# taximeter.net
KiCad netlist of a schematic drawn in Altium Designer
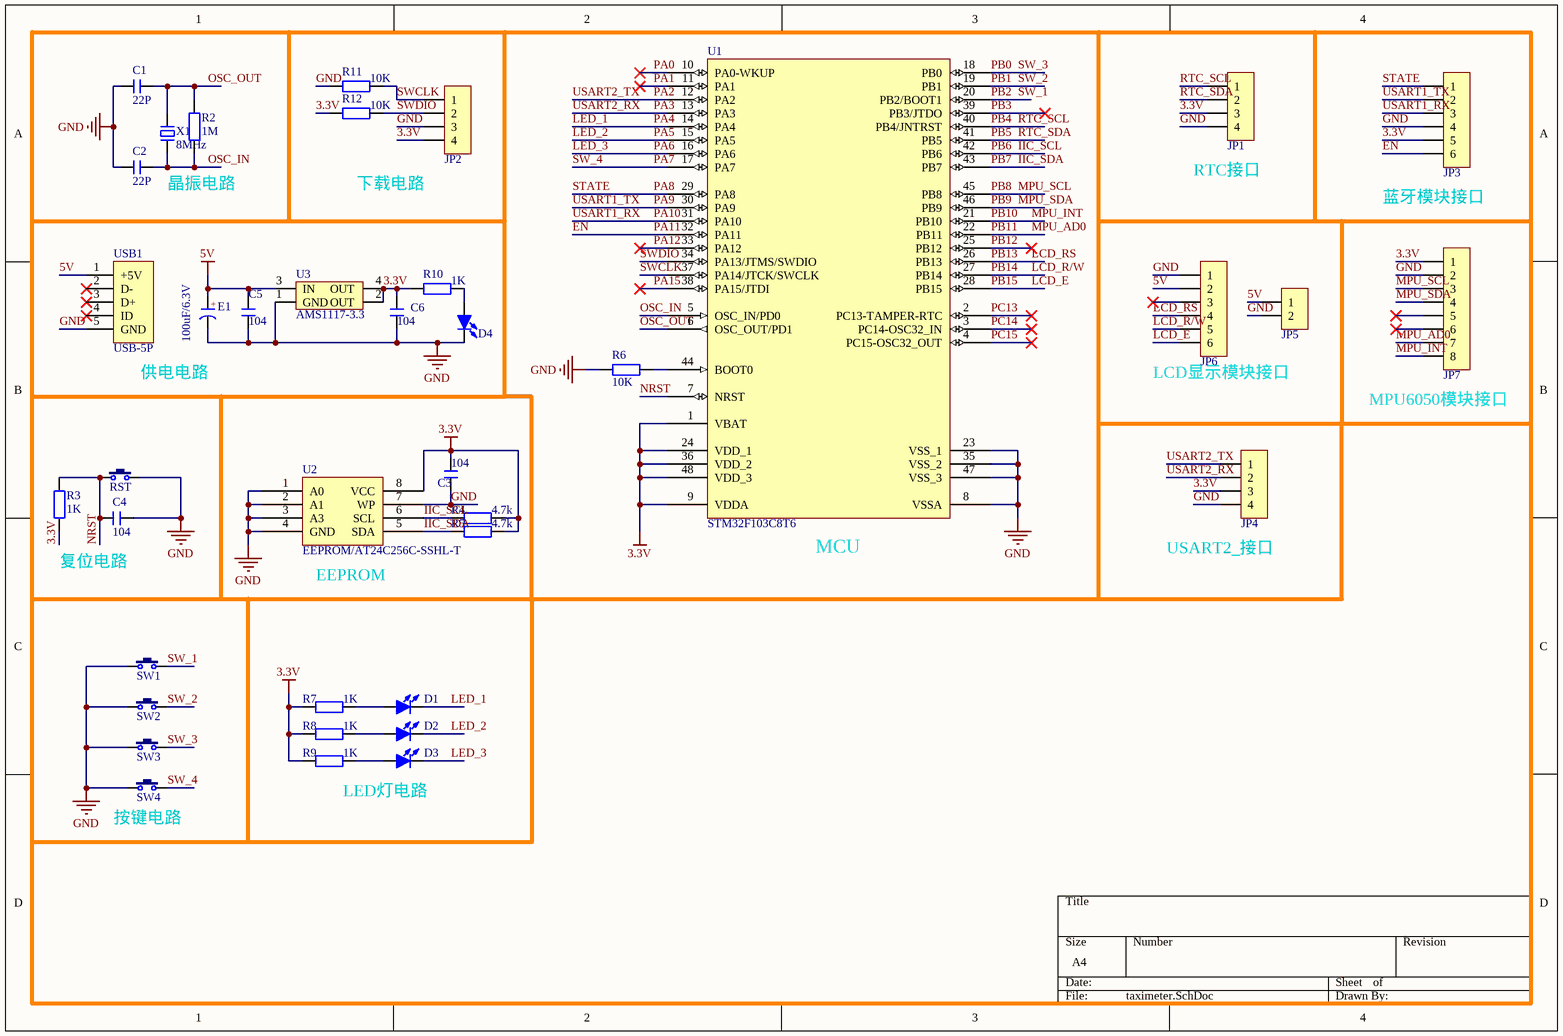
[diagram p0: taximeter.SchDoc]

(export (version "E")
  (design (tool "Eeschema 10.0.6"))
  (components
    (comp (ref "C1")
      (value "22P")
      (footprint "C 0805")
      (description "无极性贴片电容")
      (fields (field (name "版权归属") "源创客"))
      (libsource (lib "电阻-电容-电感") (part "C"))
    )
    (comp (ref "C2")
      (value "22P")
      (footprint "C 0805")
      (description "无极性贴片电容")
      (fields (field (name "版权归属") "源创客"))
      (libsource (lib "电阻-电容-电感") (part "C"))
    )
    (comp (ref "C3")
      (value "104")
      (footprint "C 0805")
      (description "无极性贴片电容")
      (fields (field (name "版权归属") "源创客"))
      (libsource (lib "电阻-电容-电感") (part "C"))
    )
    (comp (ref "C4")
      (value "104")
      (footprint "C 0805")
      (description "无极性贴片电容")
      (fields (field (name "版权归属") "源创客"))
      (libsource (lib "电阻-电容-电感") (part "C"))
    )
    (comp (ref "C5")
      (value "104")
      (footprint "C 0805")
      (description "无极性贴片电容")
      (fields (field (name "版权归属") "源创客"))
      (libsource (lib "电阻-电容-电感") (part "C"))
    )
    (comp (ref "C6")
      (value "104")
      (footprint "C 0805")
      (description "无极性贴片电容")
      (fields (field (name "版权归属") "源创客"))
      (libsource (lib "电阻-电容-电感") (part "C"))
    )
    (comp (ref "D1")
      (value "蓝色")
      (footprint "LED 0805G")
      (description "贴片LED")
      (fields (field (name "版权归属") "源创客"))
      (libsource (lib "LED") (part "LED-SMD"))
    )
    (comp (ref "D2")
      (value "蓝色")
      (footprint "LED 0805G")
      (description "贴片LED")
      (fields (field (name "版权归属") "源创客"))
      (libsource (lib "LED") (part "LED-SMD"))
    )
    (comp (ref "D3")
      (value "蓝色")
      (footprint "LED 0805G")
      (description "贴片LED")
      (fields (field (name "版权归属") "源创客"))
      (libsource (lib "LED") (part "LED-SMD"))
    )
    (comp (ref "D4")
      (value "红色")
      (footprint "LED 0805G")
      (description "贴片LED")
      (fields (field (name "版权归属") "源创客"))
      (libsource (lib "LED") (part "LED-SMD"))
    )
    (comp (ref "E1")
      (value "100uF/6.3V")
      (footprint "CD A(3216)")
      (description "贴片钽电容")
      (fields (field (name "版权归属") "源创客"))
      (libsource (lib "电阻-电容-电感") (part "C-CD"))
    )
    (comp (ref "JP1")
      (value "HDR-1X4")
      (footprint "HDR-1X4")
      (description "4P接插件")
      (fields (field (name "版权归属") "源创客"))
      (libsource (lib "接插件") (part "Header 4"))
    )
    (comp (ref "JP2")
      (value "HDR-1X4")
      (footprint "HDR-1X4")
      (description "4P接插件")
      (fields (field (name "版权归属") "源创客"))
      (libsource (lib "接插件") (part "Header 4"))
    )
    (comp (ref "JP3")
      (value "HDR-1X6")
      (footprint "HDR-1X6")
      (description "6P接插件")
      (fields (field (name "版权归属") "源创客"))
      (libsource (lib "接插件") (part "Header 6"))
    )
    (comp (ref "JP4")
      (value "HDR-1X4")
      (footprint "HDR-1X4")
      (description "4P接插件")
      (fields (field (name "版权归属") "源创客"))
      (libsource (lib "接插件") (part "Header 4"))
    )
    (comp (ref "JP5")
      (value "HDR-1X2")
      (footprint "HDR-1X2")
      (description "2P接插件")
      (fields (field (name "版权归属") "源创客"))
      (libsource (lib "接插件") (part "Header 2"))
    )
    (comp (ref "JP6")
      (value "HDR-1X6")
      (footprint "HDR-1X6")
      (description "6P接插件")
      (fields (field (name "版权归属") "源创客"))
      (libsource (lib "接插件") (part "Header 6"))
    )
    (comp (ref "JP7")
      (value "HDR-1X8")
      (footprint "HDR-1X8")
      (description "8P接插件")
      (fields (field (name "版权归属") "源创客"))
      (libsource (lib "接插件") (part "Header 8"))
    )
    (comp (ref "R2")
      (value "1M")
      (footprint "R 0805")
      (description "贴片电阻")
      (fields (field (name "版权归属") "源创客"))
      (libsource (lib "电阻-电容-电感") (part "R"))
    )
    (comp (ref "R3")
      (value "1K")
      (footprint "R 0805")
      (description "贴片电阻")
      (fields (field (name "版权归属") "源创客"))
      (libsource (lib "电阻-电容-电感") (part "R"))
    )
    (comp (ref "R4")
      (value "4.7k")
      (footprint "R 0805")
      (description "贴片电阻")
      (fields (field (name "版权归属") "源创客"))
      (libsource (lib "电阻-电容-电感") (part "R"))
    )
    (comp (ref "R5")
      (value "4.7k")
      (footprint "R 0805")
      (description "贴片电阻")
      (fields (field (name "版权归属") "源创客"))
      (libsource (lib "电阻-电容-电感") (part "R"))
    )
    (comp (ref "R6")
      (value "10K")
      (footprint "R 0805")
      (description "贴片电阻")
      (fields (field (name "版权归属") "源创客"))
      (libsource (lib "电阻-电容-电感") (part "R"))
    )
    (comp (ref "R7")
      (value "1K")
      (footprint "R 0805")
      (description "贴片电阻")
      (fields (field (name "版权归属") "源创客"))
      (libsource (lib "电阻-电容-电感") (part "R"))
    )
    (comp (ref "R8")
      (value "1K")
      (footprint "R 0805")
      (description "贴片电阻")
      (fields (field (name "版权归属") "源创客"))
      (libsource (lib "电阻-电容-电感") (part "R"))
    )
    (comp (ref "R9")
      (value "1K")
      (footprint "R 0805")
      (description "贴片电阻")
      (fields (field (name "版权归属") "源创客"))
      (libsource (lib "电阻-电容-电感") (part "R"))
    )
    (comp (ref "R10")
      (value "1K")
      (footprint "R 0805")
      (description "贴片电阻")
      (fields (field (name "版权归属") "源创客"))
      (libsource (lib "电阻-电容-电感") (part "R"))
    )
    (comp (ref "R11")
      (value "10K")
      (footprint "R 0805")
      (description "贴片电阻")
      (fields (field (name "版权归属") "源创客"))
      (libsource (lib "电阻-电容-电感") (part "R"))
    )
    (comp (ref "R12")
      (value "10K")
      (footprint "R 0805")
      (description "贴片电阻")
      (fields (field (name "版权归属") "源创客"))
      (libsource (lib "电阻-电容-电感") (part "R"))
    )
    (comp (ref "RST")
      (value "3x6x5")
      (footprint "TSW DIP-3*6*5_V")
      (description "3x6轻触开关")
      (fields (field (name "版权归属") "源创客"))
      (libsource (lib "按键-开关") (part "TSW 3x6"))
    )
    (comp (ref "SW1")
      (value "3x6x5")
      (footprint "TSW DIP-3*6*5_V")
      (description "3x6轻触开关")
      (fields (field (name "版权归属") "源创客"))
      (libsource (lib "按键-开关") (part "TSW 3x6"))
    )
    (comp (ref "SW2")
      (value "3x6x5")
      (footprint "TSW DIP-3*6*5_V")
      (description "3x6轻触开关")
      (fields (field (name "版权归属") "源创客"))
      (libsource (lib "按键-开关") (part "TSW 3x6"))
    )
    (comp (ref "SW3")
      (value "3x6x5")
      (footprint "TSW DIP-3*6*5_V")
      (description "3x6轻触开关")
      (fields (field (name "版权归属") "源创客"))
      (libsource (lib "按键-开关") (part "TSW 3x6"))
    )
    (comp (ref "SW4")
      (value "3x6x5")
      (footprint "TSW DIP-3*6*5_V")
      (description "3x6轻触开关")
      (fields (field (name "版权归属") "源创客"))
      (libsource (lib "按键-开关") (part "TSW 3x6"))
    )
    (comp (ref "U1")
      (value "STM32F103C8T6")
      (footprint "LQFP48 7X7_M")
      (description "Flaah:64/RAM:20/IO:36")
      (fields (field (name "版权归属") "源创客"))
      (libsource (lib "STM32系列单片机") (part "STM32F103C8T6"))
    )
    (comp (ref "U2")
      (value "EEPROM/AT24C256C-SSHL-T")
      (footprint "LC-SOIC-8_150mil")
      (description "EEPROM")
      (libsource (lib "Miscellaneous Devices LC") (part "EEPROM/AT24C256C-SSHL-T"))
    )
    (comp (ref "U3")
      (value "AMS1117-3.3")
      (footprint "AMS1117")
      (libsource (lib "ATK-VS1053 MP3") (part "AMS1117"))
    )
    (comp (ref "USB1")
      (value "USB-5P")
      (footprint "USB-MICRO_B")
      (description "微型USB母座")
      (fields (field (name "版权归属") "源创客"))
      (libsource (lib "接口类") (part "USB-5P"))
    )
    (comp (ref "X1")
      (value "8MHz")
      (footprint "XTAL-49S SMD")
      (description "2脚晶振")
      (fields (field (name "版权归属") "源创客"))
      (libsource (lib "保险丝-晶振") (part "XTAL-2"))
    )
  )
  (nets
    (net (code "1") (name "/EN") (class "Default")
      (node (ref "JP3") (pin "6") (pinfunction "6_6") (pintype "passive"))
      (node (ref "U1") (pin "32") (pinfunction "PA11_32") (pintype "bidirectional"))
    )
    (net (code "2") (name "/IIC_SCL") (class "Default")
      (node (ref "R4") (pin "1") (pinfunction "1_1") (pintype "passive"))
      (node (ref "U1") (pin "42") (pinfunction "PB6_42") (pintype "bidirectional"))
      (node (ref "U2") (pin "6") (pinfunction "SCL_6") (pintype "passive"))
    )
    (net (code "3") (name "/IIC_SDA") (class "Default")
      (node (ref "R5") (pin "1") (pinfunction "1_1") (pintype "passive"))
      (node (ref "U1") (pin "43") (pinfunction "PB7_43") (pintype "bidirectional"))
      (node (ref "U2") (pin "5") (pinfunction "SDA_5") (pintype "passive"))
    )
    (net (code "4") (name "/LCD_E") (class "Default")
      (node (ref "JP6") (pin "6") (pinfunction "6_6") (pintype "passive"))
      (node (ref "U1") (pin "28") (pinfunction "PB15_28") (pintype "bidirectional"))
    )
    (net (code "5") (name "/LCD_RS") (class "Default")
      (node (ref "JP6") (pin "4") (pinfunction "4_4") (pintype "passive"))
      (node (ref "U1") (pin "26") (pinfunction "PB13_26") (pintype "bidirectional"))
    )
    (net (code "6") (name "/LCD_R{slash}W") (class "Default")
      (node (ref "JP6") (pin "5") (pinfunction "5_5") (pintype "passive"))
      (node (ref "U1") (pin "27") (pinfunction "PB14_27") (pintype "bidirectional"))
    )
    (net (code "7") (name "/LED_1") (class "Default")
      (node (ref "D1") (pin "2") (pinfunction "K_2") (pintype "passive"))
      (node (ref "U1") (pin "14") (pinfunction "PA4_14") (pintype "bidirectional"))
    )
    (net (code "8") (name "/LED_2") (class "Default")
      (node (ref "D2") (pin "2") (pinfunction "K_2") (pintype "passive"))
      (node (ref "U1") (pin "15") (pinfunction "PA5_15") (pintype "bidirectional"))
    )
    (net (code "9") (name "/LED_3") (class "Default")
      (node (ref "D3") (pin "2") (pinfunction "K_2") (pintype "passive"))
      (node (ref "U1") (pin "16") (pinfunction "PA6_16") (pintype "bidirectional"))
    )
    (net (code "10") (name "/MPU_AD0") (class "Default")
      (node (ref "JP7") (pin "7") (pinfunction "7_7") (pintype "passive"))
      (node (ref "U1") (pin "22") (pinfunction "PB11_22") (pintype "bidirectional"))
    )
    (net (code "11") (name "/MPU_INT") (class "Default")
      (node (ref "JP7") (pin "8") (pinfunction "8_8") (pintype "passive"))
      (node (ref "U1") (pin "21") (pinfunction "PB10_21") (pintype "bidirectional"))
    )
    (net (code "12") (name "/MPU_SCL") (class "Default")
      (node (ref "JP7") (pin "3") (pinfunction "3_3") (pintype "passive"))
      (node (ref "U1") (pin "45") (pinfunction "PB8_45") (pintype "bidirectional"))
    )
    (net (code "13") (name "/MPU_SDA") (class "Default")
      (node (ref "JP7") (pin "4") (pinfunction "4_4") (pintype "passive"))
      (node (ref "U1") (pin "46") (pinfunction "PB9_46") (pintype "bidirectional"))
    )
    (net (code "14") (name "/NRST") (class "Default")
      (node (ref "C4") (pin "1") (pinfunction "1_1") (pintype "passive"))
      (node (ref "R3") (pin "2") (pinfunction "2_2") (pintype "passive"))
      (node (ref "RST") (pin "1") (pinfunction "1_1") (pintype "passive"))
      (node (ref "U1") (pin "7") (pinfunction "NRST_7") (pintype "bidirectional"))
    )
    (net (code "15") (name "/OSC_IN") (class "Default")
      (node (ref "C2") (pin "2") (pinfunction "2_2") (pintype "passive"))
      (node (ref "R2") (pin "2") (pinfunction "2_2") (pintype "passive"))
      (node (ref "U1") (pin "5") (pinfunction "OSC_IN/PD0_5") (pintype "input"))
      (node (ref "X1") (pin "2") (pinfunction "2_2") (pintype "passive"))
    )
    (net (code "16") (name "/OSC_OUT") (class "Default")
      (node (ref "C1") (pin "2") (pinfunction "2_2") (pintype "passive"))
      (node (ref "R2") (pin "1") (pinfunction "1_1") (pintype "passive"))
      (node (ref "U1") (pin "6") (pinfunction "OSC_OUT/PD1_6") (pintype "output"))
      (node (ref "X1") (pin "1") (pinfunction "1_1") (pintype "passive"))
    )
    (net (code "17") (name "/PA0") (class "Default")
      (node (ref "U1") (pin "10") (pinfunction "PA0-WKUP_10") (pintype "bidirectional+no_connect"))
    )
    (net (code "18") (name "/PA1") (class "Default")
      (node (ref "U1") (pin "11") (pinfunction "PA1_11") (pintype "bidirectional+no_connect"))
    )
    (net (code "19") (name "/PA2") (class "Default")
      (node (ref "JP4") (pin "1") (pinfunction "1_1") (pintype "passive"))
      (node (ref "U1") (pin "12") (pinfunction "PA2_12") (pintype "bidirectional"))
    )
    (net (code "20") (name "/PA3") (class "Default")
      (node (ref "JP4") (pin "2") (pinfunction "2_2") (pintype "passive"))
      (node (ref "U1") (pin "13") (pinfunction "PA3_13") (pintype "bidirectional"))
    )
    (net (code "21") (name "/PA7") (class "Default")
      (node (ref "SW4") (pin "2") (pinfunction "2_2") (pintype "passive"))
      (node (ref "U1") (pin "17") (pinfunction "PA7_17") (pintype "bidirectional"))
    )
    (net (code "22") (name "/PA8") (class "Default")
      (node (ref "JP3") (pin "1") (pinfunction "1_1") (pintype "passive"))
      (node (ref "U1") (pin "29") (pinfunction "PA8_29") (pintype "bidirectional"))
    )
    (net (code "23") (name "/PA9") (class "Default")
      (node (ref "JP3") (pin "2") (pinfunction "2_2") (pintype "passive"))
      (node (ref "U1") (pin "30") (pinfunction "PA9_30") (pintype "bidirectional"))
    )
    (net (code "24") (name "/PA10") (class "Default")
      (node (ref "JP3") (pin "3") (pinfunction "3_3") (pintype "passive"))
      (node (ref "U1") (pin "31") (pinfunction "PA10_31") (pintype "bidirectional"))
    )
    (net (code "25") (name "/PA12") (class "Default")
      (node (ref "U1") (pin "33") (pinfunction "PA12_33") (pintype "bidirectional+no_connect"))
    )
    (net (code "26") (name "/PA15") (class "Default")
      (node (ref "U1") (pin "38") (pinfunction "PA15/JTDI_38") (pintype "bidirectional+no_connect"))
    )
    (net (code "27") (name "/PB0") (class "Default")
      (node (ref "SW3") (pin "2") (pinfunction "2_2") (pintype "passive"))
      (node (ref "U1") (pin "18") (pinfunction "PB0_18") (pintype "bidirectional"))
    )
    (net (code "28") (name "/PB1") (class "Default")
      (node (ref "SW2") (pin "2") (pinfunction "2_2") (pintype "passive"))
      (node (ref "U1") (pin "19") (pinfunction "PB1_19") (pintype "bidirectional"))
    )
    (net (code "29") (name "/PB2") (class "Default")
      (node (ref "SW1") (pin "2") (pinfunction "2_2") (pintype "passive"))
      (node (ref "U1") (pin "20") (pinfunction "PB2/BOOT1_20") (pintype "bidirectional"))
    )
    (net (code "30") (name "/PB3") (class "Default")
      (node (ref "U1") (pin "39") (pinfunction "PB3/JTDO_39") (pintype "bidirectional+no_connect"))
    )
    (net (code "31") (name "/PB4") (class "Default")
      (node (ref "JP1") (pin "1") (pinfunction "1_1") (pintype "passive"))
      (node (ref "U1") (pin "40") (pinfunction "PB4/JNTRST_40") (pintype "bidirectional"))
    )
    (net (code "32") (name "/PB5") (class "Default")
      (node (ref "JP1") (pin "2") (pinfunction "2_2") (pintype "passive"))
      (node (ref "U1") (pin "41") (pinfunction "PB5_41") (pintype "bidirectional"))
    )
    (net (code "33") (name "/PB12") (class "Default")
      (node (ref "U1") (pin "25") (pinfunction "PB12_25") (pintype "bidirectional+no_connect"))
    )
    (net (code "34") (name "/PC13") (class "Default")
      (node (ref "U1") (pin "2") (pinfunction "PC13-TAMPER-RTC_2") (pintype "bidirectional+no_connect"))
    )
    (net (code "35") (name "/PC14") (class "Default")
      (node (ref "U1") (pin "3") (pinfunction "PC14-OSC32_IN_3") (pintype "bidirectional+no_connect"))
    )
    (net (code "36") (name "/PC15") (class "Default")
      (node (ref "U1") (pin "4") (pinfunction "PC15-OSC32_OUT_4") (pintype "bidirectional+no_connect"))
    )
    (net (code "37") (name "/SWCLK") (class "Default")
      (node (ref "JP2") (pin "1") (pinfunction "1_1") (pintype "passive"))
      (node (ref "R11") (pin "2") (pinfunction "2_2") (pintype "passive"))
      (node (ref "U1") (pin "37") (pinfunction "PA14/JTCK/SWCLK_37") (pintype "bidirectional"))
    )
    (net (code "38") (name "/SWDIO") (class "Default")
      (node (ref "JP2") (pin "2") (pinfunction "2_2") (pintype "passive"))
      (node (ref "R12") (pin "2") (pinfunction "2_2") (pintype "passive"))
      (node (ref "U1") (pin "34") (pinfunction "PA13/JTMS/SWDIO_34") (pintype "bidirectional"))
    )
    (net (code "39") (name "3.3V") (class "Default")
      (node (ref "C3") (pin "2") (pinfunction "2_2") (pintype "passive"))
      (node (ref "C6") (pin "2") (pinfunction "2_2") (pintype "passive"))
      (node (ref "JP1") (pin "3") (pinfunction "3_3") (pintype "passive"))
      (node (ref "JP2") (pin "4") (pinfunction "4_4") (pintype "passive"))
      (node (ref "JP3") (pin "5") (pinfunction "5_5") (pintype "passive"))
      (node (ref "JP4") (pin "3") (pinfunction "3_3") (pintype "passive"))
      (node (ref "JP7") (pin "1") (pinfunction "1_1") (pintype "passive"))
      (node (ref "R10") (pin "1") (pinfunction "1_1") (pintype "passive"))
      (node (ref "R12") (pin "1") (pinfunction "1_1") (pintype "passive"))
      (node (ref "R3") (pin "1") (pinfunction "1_1") (pintype "passive"))
      (node (ref "R4") (pin "2") (pinfunction "2_2") (pintype "passive"))
      (node (ref "R5") (pin "2") (pinfunction "2_2") (pintype "passive"))
      (node (ref "R7") (pin "2") (pinfunction "2_2") (pintype "passive"))
      (node (ref "R8") (pin "2") (pinfunction "2_2") (pintype "passive"))
      (node (ref "R9") (pin "2") (pinfunction "2_2") (pintype "passive"))
      (node (ref "U1") (pin "1") (pinfunction "VBAT_1") (pintype "power_in"))
      (node (ref "U1") (pin "24") (pinfunction "VDD_1_24") (pintype "power_in"))
      (node (ref "U1") (pin "36") (pinfunction "VDD_2_36") (pintype "power_in"))
      (node (ref "U1") (pin "48") (pinfunction "VDD_3_48") (pintype "power_in"))
      (node (ref "U1") (pin "9") (pinfunction "VDDA_9") (pintype "power_in"))
      (node (ref "U2") (pin "8") (pinfunction "VCC_8") (pintype "passive"))
      (node (ref "U3") (pin "2") (pinfunction "OUT_2") (pintype "passive"))
      (node (ref "U3") (pin "4") (pinfunction "OUT_4") (pintype "passive"))
    )
    (net (code "40") (name "5V") (class "Default")
      (node (ref "C5") (pin "2") (pinfunction "2_2") (pintype "passive"))
      (node (ref "E1") (pin "1") (pinfunction "A_1") (pintype "passive"))
      (node (ref "JP5") (pin "1") (pinfunction "1_1") (pintype "passive"))
      (node (ref "JP6") (pin "2") (pinfunction "2_2") (pintype "passive"))
      (node (ref "U3") (pin "3") (pinfunction "IN_3") (pintype "passive"))
      (node (ref "USB1") (pin "1") (pinfunction "+5V_1") (pintype "passive"))
    )
    (net (code "41") (name "GND") (class "Default")
      (node (ref "C1") (pin "1") (pinfunction "1_1") (pintype "passive"))
      (node (ref "C2") (pin "1") (pinfunction "1_1") (pintype "passive"))
      (node (ref "C3") (pin "1") (pinfunction "1_1") (pintype "passive"))
      (node (ref "C4") (pin "2") (pinfunction "2_2") (pintype "passive"))
      (node (ref "C5") (pin "1") (pinfunction "1_1") (pintype "passive"))
      (node (ref "C6") (pin "1") (pinfunction "1_1") (pintype "passive"))
      (node (ref "D4") (pin "2") (pinfunction "K_2") (pintype "passive"))
      (node (ref "E1") (pin "2") (pinfunction "K_2") (pintype "passive"))
      (node (ref "JP1") (pin "4") (pinfunction "4_4") (pintype "passive"))
      (node (ref "JP2") (pin "3") (pinfunction "3_3") (pintype "passive"))
      (node (ref "JP3") (pin "4") (pinfunction "4_4") (pintype "passive"))
      (node (ref "JP4") (pin "4") (pinfunction "4_4") (pintype "passive"))
      (node (ref "JP5") (pin "2") (pinfunction "2_2") (pintype "passive"))
      (node (ref "JP6") (pin "1") (pinfunction "1_1") (pintype "passive"))
      (node (ref "JP7") (pin "2") (pinfunction "2_2") (pintype "passive"))
      (node (ref "R11") (pin "1") (pinfunction "1_1") (pintype "passive"))
      (node (ref "R6") (pin "1") (pinfunction "1_1") (pintype "passive"))
      (node (ref "RST") (pin "2") (pinfunction "2_2") (pintype "passive"))
      (node (ref "SW1") (pin "1") (pinfunction "1_1") (pintype "passive"))
      (node (ref "SW2") (pin "1") (pinfunction "1_1") (pintype "passive"))
      (node (ref "SW3") (pin "1") (pinfunction "1_1") (pintype "passive"))
      (node (ref "SW4") (pin "1") (pinfunction "1_1") (pintype "passive"))
      (node (ref "U1") (pin "23") (pinfunction "VSS_1_23") (pintype "power_in"))
      (node (ref "U1") (pin "35") (pinfunction "VSS_2_35") (pintype "power_in"))
      (node (ref "U1") (pin "47") (pinfunction "VSS_3_47") (pintype "power_in"))
      (node (ref "U1") (pin "8") (pinfunction "VSSA_8") (pintype "power_in"))
      (node (ref "U2") (pin "1") (pinfunction "A0_1") (pintype "passive"))
      (node (ref "U2") (pin "2") (pinfunction "A1_2") (pintype "passive"))
      (node (ref "U2") (pin "3") (pinfunction "A3_3") (pintype "passive"))
      (node (ref "U2") (pin "4") (pinfunction "GND_4") (pintype "passive"))
      (node (ref "U2") (pin "7") (pinfunction "WP_7") (pintype "passive"))
      (node (ref "U3") (pin "1") (pinfunction "GND_1") (pintype "passive"))
      (node (ref "USB1") (pin "5") (pinfunction "GND_5") (pintype "passive"))
    )
    (net (code "42") (name "Net-(D1-A)") (class "Default")
      (node (ref "D1") (pin "1") (pinfunction "A_1") (pintype "passive"))
      (node (ref "R7") (pin "1") (pinfunction "1_1") (pintype "passive"))
    )
    (net (code "43") (name "Net-(D2-A)") (class "Default")
      (node (ref "D2") (pin "1") (pinfunction "A_1") (pintype "passive"))
      (node (ref "R8") (pin "1") (pinfunction "1_1") (pintype "passive"))
    )
    (net (code "44") (name "Net-(D3-A)") (class "Default")
      (node (ref "D3") (pin "1") (pinfunction "A_1") (pintype "passive"))
      (node (ref "R9") (pin "1") (pinfunction "1_1") (pintype "passive"))
    )
    (net (code "45") (name "Net-(D4-A)") (class "Default")
      (node (ref "D4") (pin "1") (pinfunction "A_1") (pintype "passive"))
      (node (ref "R10") (pin "2") (pinfunction "2_2") (pintype "passive"))
    )
    (net (code "46") (name "Net-(U1-BOOT0)") (class "Default")
      (node (ref "R6") (pin "2") (pinfunction "2_2") (pintype "passive"))
      (node (ref "U1") (pin "44") (pinfunction "BOOT0_44") (pintype "input"))
    )
    (net (code "47") (name "unconnected-(JP6-Pad3)") (class "Default")
      (node (ref "JP6") (pin "3") (pinfunction "3_3") (pintype "passive+no_connect"))
    )
    (net (code "48") (name "unconnected-(JP7-Pad5)") (class "Default")
      (node (ref "JP7") (pin "5") (pinfunction "5_5") (pintype "passive+no_connect"))
    )
    (net (code "49") (name "unconnected-(JP7-Pad6)") (class "Default")
      (node (ref "JP7") (pin "6") (pinfunction "6_6") (pintype "passive+no_connect"))
    )
    (net (code "50") (name "unconnected-(USB1-D+-Pad3)") (class "Default")
      (node (ref "USB1") (pin "3") (pinfunction "D+_3") (pintype "passive+no_connect"))
    )
    (net (code "51") (name "unconnected-(USB1-D--Pad2)") (class "Default")
      (node (ref "USB1") (pin "2") (pinfunction "D-_2") (pintype "passive+no_connect"))
    )
    (net (code "52") (name "unconnected-(USB1-ID-Pad4)") (class "Default")
      (node (ref "USB1") (pin "4") (pinfunction "ID_4") (pintype "passive+no_connect"))
    )
  )
)
